# TraitementNumerique.net
KiCad netlist of a schematic drawn in Altium Designer
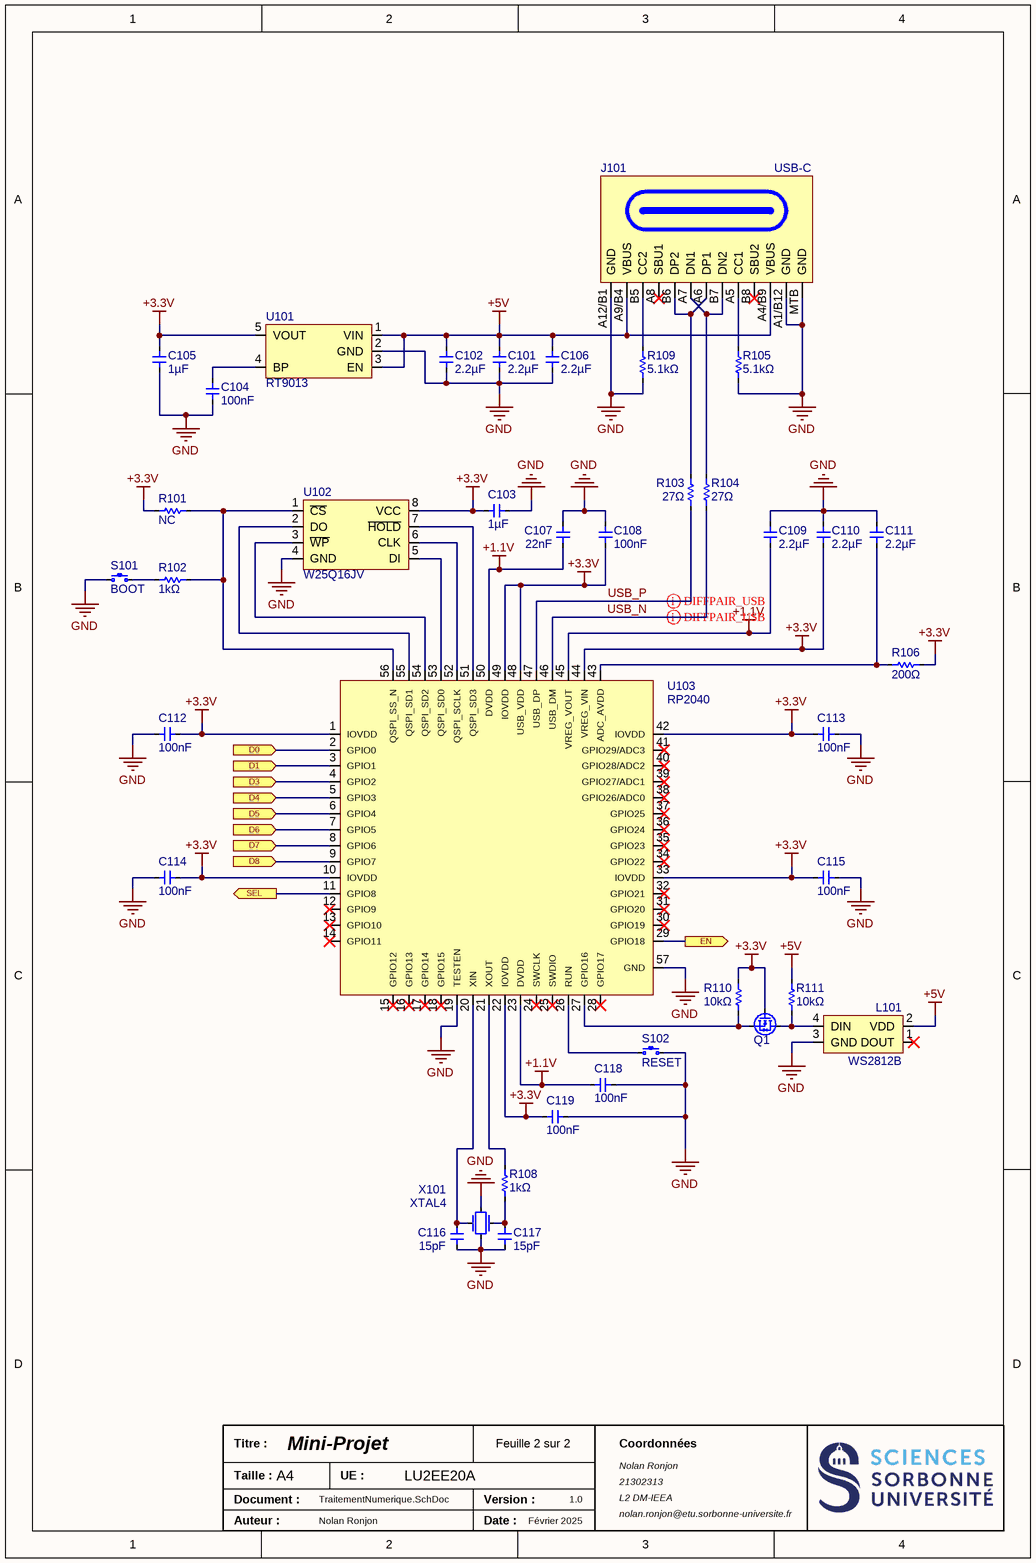
[diagram p0: TraitementNumerique.SchDoc]

(export (version "E")
  (design (tool "Eeschema 10.0.6"))
  (components
    (comp (ref "C101")
      (value "2.2µF")
      (footprint "0603")
      (description "Condensateur")
      (libsource (lib "LU2EE20A") (part "Condensateur"))
    )
    (comp (ref "C102")
      (value "2.2µF")
      (footprint "0603")
      (description "Condensateur")
      (libsource (lib "LU2EE20A") (part "Condensateur"))
    )
    (comp (ref "C103")
      (value "1µF")
      (footprint "0603")
      (description "Condensateur")
      (libsource (lib "LU2EE20A") (part "Condensateur"))
    )
    (comp (ref "C104")
      (value "100nF")
      (footprint "0603")
      (description "Condensateur")
      (libsource (lib "LU2EE20A") (part "Condensateur"))
    )
    (comp (ref "C105")
      (value "1µF")
      (footprint "0603")
      (description "Condensateur")
      (libsource (lib "LU2EE20A") (part "Condensateur"))
    )
    (comp (ref "C106")
      (value "2.2µF")
      (footprint "0603")
      (description "Condensateur")
      (libsource (lib "LU2EE20A") (part "Condensateur"))
    )
    (comp (ref "C107")
      (value "22nF")
      (footprint "0603")
      (description "Condensateur")
      (libsource (lib "LU2EE20A") (part "Condensateur"))
    )
    (comp (ref "C108")
      (value "100nF")
      (footprint "0603")
      (description "Condensateur")
      (libsource (lib "LU2EE20A") (part "Condensateur"))
    )
    (comp (ref "C109")
      (value "2.2µF")
      (footprint "0603")
      (description "Condensateur")
      (libsource (lib "LU2EE20A") (part "Condensateur"))
    )
    (comp (ref "C110")
      (value "2.2µF")
      (footprint "0603")
      (description "Condensateur")
      (libsource (lib "LU2EE20A") (part "Condensateur"))
    )
    (comp (ref "C111")
      (value "2.2µF")
      (footprint "0603")
      (description "Condensateur")
      (libsource (lib "LU2EE20A") (part "Condensateur"))
    )
    (comp (ref "C112")
      (value "100nF")
      (footprint "0603")
      (description "Condensateur")
      (libsource (lib "LU2EE20A") (part "Condensateur"))
    )
    (comp (ref "C113")
      (value "100nF")
      (footprint "0603")
      (description "Condensateur")
      (libsource (lib "LU2EE20A") (part "Condensateur"))
    )
    (comp (ref "C114")
      (value "100nF")
      (footprint "0603")
      (description "Condensateur")
      (libsource (lib "LU2EE20A") (part "Condensateur"))
    )
    (comp (ref "C115")
      (value "100nF")
      (footprint "0603")
      (description "Condensateur")
      (libsource (lib "LU2EE20A") (part "Condensateur"))
    )
    (comp (ref "C116")
      (value "15pF")
      (footprint "0603")
      (description "Condensateur")
      (libsource (lib "LU2EE20A") (part "Condensateur"))
    )
    (comp (ref "C117")
      (value "15pF")
      (footprint "0603")
      (description "Condensateur")
      (libsource (lib "LU2EE20A") (part "Condensateur"))
    )
    (comp (ref "C118")
      (value "100nF")
      (footprint "0603")
      (description "Condensateur")
      (libsource (lib "LU2EE20A") (part "Condensateur"))
    )
    (comp (ref "C119")
      (value "100nF")
      (footprint "0603")
      (description "Condensateur")
      (libsource (lib "LU2EE20A") (part "Condensateur"))
    )
    (comp (ref "J101")
      (value "USB-C")
      (footprint "USB-C")
      (description "Connecteur")
      (fields (field (name "MANUFACTURER PART") "TYPE-C-31-M-12") (field (name "JLCPCB PART") "C165948"))
      (libsource (lib "LU2EE20A") (part "USB-C"))
    )
    (comp (ref "L101")
      (value "WS2812B")
      (footprint "SMD1615")
      (description "LED RGB")
      (fields
        (field (name "MANUFACTURER PART") "XL-1615RGBC-WS2812B")
        (field (name "JLCPCB PART") "C5349954")
      )
      (libsource (lib "LU2EE20A") (part "WS2812B"))
    )
    (comp (ref "Q1")
      (value "2N7002")
      (footprint "SOT-23")
      (description "MOSFET")
      (fields (field (name "MANUFACTURER PART") "2N7002K-7") (field (name "JLCPCB PART") "C85047"))
      (libsource (lib "LU2EE20A") (part "2N7002"))
    )
    (comp (ref "R101")
      (value "NC")
      (footprint "0603")
      (description "Resistance")
      (libsource (lib "LU2EE20A") (part "Resistance"))
    )
    (comp (ref "R102")
      (value "1kΩ")
      (footprint "0603")
      (description "Resistance")
      (libsource (lib "LU2EE20A") (part "Resistance"))
    )
    (comp (ref "R103")
      (value "27Ω")
      (footprint "0603")
      (description "Resistance")
      (libsource (lib "LU2EE20A") (part "Resistance"))
    )
    (comp (ref "R104")
      (value "27Ω")
      (footprint "0603")
      (description "Resistance")
      (libsource (lib "LU2EE20A") (part "Resistance"))
    )
    (comp (ref "R105")
      (value "5.1kΩ")
      (footprint "0603")
      (description "Resistance")
      (libsource (lib "LU2EE20A") (part "Resistance"))
    )
    (comp (ref "R106")
      (value "200Ω")
      (footprint "0603")
      (description "Resistance")
      (libsource (lib "LU2EE20A") (part "Resistance"))
    )
    (comp (ref "R108")
      (value "1kΩ")
      (footprint "0603")
      (description "Resistance")
      (libsource (lib "LU2EE20A") (part "Resistance"))
    )
    (comp (ref "R109")
      (value "5.1kΩ")
      (footprint "0603")
      (description "Resistance")
      (libsource (lib "LU2EE20A") (part "Resistance"))
    )
    (comp (ref "R110")
      (value "10kΩ")
      (footprint "0603")
      (description "Resistance")
      (libsource (lib "LU2EE20A") (part "Resistance"))
    )
    (comp (ref "R111")
      (value "10kΩ")
      (footprint "0603")
      (description "Resistance")
      (libsource (lib "LU2EE20A") (part "Resistance"))
    )
    (comp (ref "S101")
      (value "BOOT")
      (footprint "Bouton")
      (description "Bouton")
      (fields (field (name "MANUFACTURER PART") "TS-1088-AR02016") (field (name "JLCPCB PART") "C720477"))
      (libsource (lib "LU2EE20A") (part "Bouton"))
    )
    (comp (ref "S102")
      (value "RESET")
      (footprint "Bouton")
      (description "Bouton")
      (fields (field (name "MANUFACTURER PART") "TS-1088-AR02016") (field (name "JLCPCB PART") "C720477"))
      (libsource (lib "LU2EE20A") (part "Bouton"))
    )
    (comp (ref "U101")
      (value "RT9013")
      (footprint "SOT-23-5")
      (description "Régulateur de tension")
      (fields (field (name "MANUFACTURER PART") "RT9013-33GB") (field (name "JLCPCB PART") "C47773"))
      (libsource (lib "LU2EE20A") (part "RT9013"))
    )
    (comp (ref "U102")
      (value "W25Q16JV")
      (footprint "USON-8")
      (description "Flash")
      (fields (field (name "MANUFACTURER PART") "W25Q16JVUXIQ") (field (name "JLCPCB PART") "C2843335"))
      (libsource (lib "LU2EE20A") (part "W25Q16JV"))
    )
    (comp (ref "U103")
      (value "RP2040")
      (footprint "QFN-56")
      (description "Microcontroleur")
      (fields (field (name "JLCPCB PART") "C2040"))
      (libsource (lib "LU2EE20A") (part "RP2040"))
    )
    (comp (ref "X101")
      (value "XTAL4")
      (footprint "SMD3225")
      (description "Crystal")
      (fields (field (name "MANUFACTURER PART") "ABM8-272-T3") (field (name "JLCPCB PART") "C20625731"))
      (libsource (lib "LU2EE20A") (part "XTAL4"))
    )
  )
  (nets
    (net (code "1") (name "+1.1V") (class "Default")
      (node (ref "C107") (pin "2") (pinfunction "2_2") (pintype "passive"))
      (node (ref "C109") (pin "2") (pinfunction "2_2") (pintype "passive"))
      (node (ref "C118") (pin "2") (pinfunction "2_2") (pintype "passive"))
      (node (ref "U103") (pin "23") (pinfunction "DVDD_23") (pintype "passive"))
      (node (ref "U103") (pin "45") (pinfunction "VREG_VOUT_45") (pintype "passive"))
      (node (ref "U103") (pin "50") (pinfunction "DVDD_50") (pintype "passive"))
    )
    (net (code "2") (name "+3.3V") (class "Default")
      (node (ref "C103") (pin "2") (pinfunction "2_2") (pintype "passive"))
      (node (ref "C105") (pin "1") (pinfunction "1_1") (pintype "passive"))
      (node (ref "C108") (pin "2") (pinfunction "2_2") (pintype "passive"))
      (node (ref "C110") (pin "2") (pinfunction "2_2") (pintype "passive"))
      (node (ref "C112") (pin "2") (pinfunction "2_2") (pintype "passive"))
      (node (ref "C113") (pin "2") (pinfunction "2_2") (pintype "passive"))
      (node (ref "C114") (pin "2") (pinfunction "2_2") (pintype "passive"))
      (node (ref "C115") (pin "2") (pinfunction "2_2") (pintype "passive"))
      (node (ref "C119") (pin "2") (pinfunction "2_2") (pintype "passive"))
      (node (ref "Q1") (pin "1") (pinfunction "G_1") (pintype "passive"))
      (node (ref "R101") (pin "2") (pinfunction "2_2") (pintype "passive"))
      (node (ref "R106") (pin "1") (pinfunction "1_1") (pintype "passive"))
      (node (ref "R110") (pin "2") (pinfunction "2_2") (pintype "passive"))
      (node (ref "U101") (pin "5") (pinfunction "VOUT_5") (pintype "passive"))
      (node (ref "U102") (pin "8") (pinfunction "VCC_8") (pintype "passive"))
      (node (ref "U103") (pin "1") (pinfunction "IOVDD_1") (pintype "passive"))
      (node (ref "U103") (pin "10") (pinfunction "IOVDD_10") (pintype "passive"))
      (node (ref "U103") (pin "22") (pinfunction "IOVDD_22") (pintype "passive"))
      (node (ref "U103") (pin "33") (pinfunction "IOVDD_33") (pintype "passive"))
      (node (ref "U103") (pin "42") (pinfunction "IOVDD_42") (pintype "passive"))
      (node (ref "U103") (pin "44") (pinfunction "VREG_VIN_44") (pintype "passive"))
      (node (ref "U103") (pin "48") (pinfunction "USB_VDD_48") (pintype "passive"))
      (node (ref "U103") (pin "49") (pinfunction "IOVDD_49") (pintype "passive"))
    )
    (net (code "3") (name "+5V") (class "Default")
      (node (ref "C101") (pin "1") (pinfunction "1_1") (pintype "passive"))
      (node (ref "C102") (pin "1") (pinfunction "1_1") (pintype "passive"))
      (node (ref "C106") (pin "1") (pinfunction "1_1") (pintype "passive"))
      (node (ref "J101") (pin "A4/B9") (pinfunction "VBUS_A4/B9") (pintype "passive"))
      (node (ref "J101") (pin "A9/B4") (pinfunction "VBUS_A9/B4") (pintype "passive"))
      (node (ref "L101") (pin "2") (pinfunction "VDD_2") (pintype "passive"))
      (node (ref "R111") (pin "2") (pinfunction "2_2") (pintype "passive"))
      (node (ref "U101") (pin "1") (pinfunction "VIN_1") (pintype "passive"))
      (node (ref "U101") (pin "3") (pinfunction "EN_3") (pintype "passive"))
    )
    (net (code "4") (name "/D0") (class "Default")
      (node (ref "U103") (pin "2") (pinfunction "GPIO0_2") (pintype "passive"))
    )
    (net (code "5") (name "/D1") (class "Default")
      (node (ref "U103") (pin "3") (pinfunction "GPIO1_3") (pintype "passive"))
    )
    (net (code "6") (name "/D3") (class "Default")
      (node (ref "U103") (pin "4") (pinfunction "GPIO2_4") (pintype "passive"))
    )
    (net (code "7") (name "/D4") (class "Default")
      (node (ref "U103") (pin "5") (pinfunction "GPIO3_5") (pintype "passive"))
    )
    (net (code "8") (name "/D5") (class "Default")
      (node (ref "U103") (pin "6") (pinfunction "GPIO4_6") (pintype "passive"))
    )
    (net (code "9") (name "/D6") (class "Default")
      (node (ref "U103") (pin "7") (pinfunction "GPIO5_7") (pintype "passive"))
    )
    (net (code "10") (name "/D7") (class "Default")
      (node (ref "U103") (pin "8") (pinfunction "GPIO6_8") (pintype "passive"))
    )
    (net (code "11") (name "/D8") (class "Default")
      (node (ref "U103") (pin "9") (pinfunction "GPIO7_9") (pintype "passive"))
    )
    (net (code "12") (name "/EN") (class "Default")
      (node (ref "U103") (pin "29") (pinfunction "GPIO18_29") (pintype "passive"))
    )
    (net (code "13") (name "/SEL") (class "Default")
      (node (ref "U103") (pin "11") (pinfunction "GPIO8_11") (pintype "passive"))
    )
    (net (code "14") (name "/USB_N") (class "Default")
      (node (ref "R104") (pin "1") (pinfunction "1_1") (pintype "passive"))
      (node (ref "U103") (pin "46") (pinfunction "USB_DM_46") (pintype "passive"))
    )
    (net (code "15") (name "/USB_P") (class "Default")
      (node (ref "R103") (pin "1") (pinfunction "1_1") (pintype "passive"))
      (node (ref "U103") (pin "47") (pinfunction "USB_DP_47") (pintype "passive"))
    )
    (net (code "16") (name "GND") (class "Default")
      (node (ref "C101") (pin "2") (pinfunction "2_2") (pintype "passive"))
      (node (ref "C102") (pin "2") (pinfunction "2_2") (pintype "passive"))
      (node (ref "C103") (pin "1") (pinfunction "1_1") (pintype "passive"))
      (node (ref "C104") (pin "2") (pinfunction "2_2") (pintype "passive"))
      (node (ref "C105") (pin "2") (pinfunction "2_2") (pintype "passive"))
      (node (ref "C106") (pin "2") (pinfunction "2_2") (pintype "passive"))
      (node (ref "C107") (pin "1") (pinfunction "1_1") (pintype "passive"))
      (node (ref "C108") (pin "1") (pinfunction "1_1") (pintype "passive"))
      (node (ref "C109") (pin "1") (pinfunction "1_1") (pintype "passive"))
      (node (ref "C110") (pin "1") (pinfunction "1_1") (pintype "passive"))
      (node (ref "C111") (pin "1") (pinfunction "1_1") (pintype "passive"))
      (node (ref "C112") (pin "1") (pinfunction "1_1") (pintype "passive"))
      (node (ref "C113") (pin "1") (pinfunction "1_1") (pintype "passive"))
      (node (ref "C114") (pin "1") (pinfunction "1_1") (pintype "passive"))
      (node (ref "C115") (pin "1") (pinfunction "1_1") (pintype "passive"))
      (node (ref "C116") (pin "2") (pinfunction "2_2") (pintype "passive"))
      (node (ref "C117") (pin "2") (pinfunction "2_2") (pintype "passive"))
      (node (ref "C118") (pin "1") (pinfunction "1_1") (pintype "passive"))
      (node (ref "C119") (pin "1") (pinfunction "1_1") (pintype "passive"))
      (node (ref "J101") (pin "A1/B12") (pinfunction "GND_A1/B12") (pintype "passive"))
      (node (ref "J101") (pin "A12/B1") (pinfunction "GND_A12/B1") (pintype "passive"))
      (node (ref "J101") (pin "MTB") (pinfunction "GND_MTB") (pintype "passive"))
      (node (ref "L101") (pin "3") (pinfunction "GND_3") (pintype "passive"))
      (node (ref "R105") (pin "1") (pinfunction "1_1") (pintype "passive"))
      (node (ref "R109") (pin "1") (pinfunction "1_1") (pintype "passive"))
      (node (ref "S101") (pin "1") (pinfunction "1_1") (pintype "passive"))
      (node (ref "S102") (pin "2") (pinfunction "2_2") (pintype "passive"))
      (node (ref "U101") (pin "2") (pinfunction "GND_2") (pintype "passive"))
      (node (ref "U102") (pin "4") (pinfunction "GND_4") (pintype "passive"))
      (node (ref "U103") (pin "19") (pinfunction "TESTEN_19") (pintype "passive"))
      (node (ref "U103") (pin "57") (pinfunction "GND_57") (pintype "passive"))
      (node (ref "X101") (pin "2") (pinfunction "GND_1_2") (pintype "passive"))
      (node (ref "X101") (pin "4") (pinfunction "GND_2_4") (pintype "passive"))
    )
    (net (code "17") (name "Net-(J101-CC1)") (class "Default")
      (node (ref "J101") (pin "A5") (pinfunction "CC1_A5") (pintype "passive"))
      (node (ref "R105") (pin "2") (pinfunction "2_2") (pintype "passive"))
    )
    (net (code "18") (name "Net-(J101-CC2)") (class "Default")
      (node (ref "J101") (pin "B5") (pinfunction "CC2_B5") (pintype "passive"))
      (node (ref "R109") (pin "2") (pinfunction "2_2") (pintype "passive"))
    )
    (net (code "19") (name "Net-(J101-DN1)") (class "Default")
      (node (ref "J101") (pin "A7") (pinfunction "DN1_A7") (pintype "passive"))
      (node (ref "J101") (pin "B7") (pinfunction "DN2_B7") (pintype "passive"))
      (node (ref "R104") (pin "2") (pinfunction "2_2") (pintype "passive"))
    )
    (net (code "20") (name "Net-(J101-DP1)") (class "Default")
      (node (ref "J101") (pin "A6") (pinfunction "DP1_A6") (pintype "passive"))
      (node (ref "J101") (pin "B6") (pinfunction "DP2_B6") (pintype "passive"))
      (node (ref "R103") (pin "2") (pinfunction "2_2") (pintype "passive"))
    )
    (net (code "21") (name "Net-(L101-DIN)") (class "Default")
      (node (ref "L101") (pin "4") (pinfunction "DIN_4") (pintype "passive"))
      (node (ref "Q1") (pin "3") (pinfunction "D_3") (pintype "passive"))
      (node (ref "R111") (pin "1") (pinfunction "1_1") (pintype "passive"))
    )
    (net (code "22") (name "Net-(Q1-S)") (class "Default")
      (node (ref "Q1") (pin "2") (pinfunction "S_2") (pintype "passive"))
      (node (ref "R110") (pin "1") (pinfunction "1_1") (pintype "passive"))
      (node (ref "U103") (pin "27") (pinfunction "GPIO16_27") (pintype "passive"))
    )
    (net (code "23") (name "Net-(R102-Pad2)") (class "Default")
      (node (ref "R102") (pin "2") (pinfunction "2_2") (pintype "passive"))
      (node (ref "S101") (pin "2") (pinfunction "2_2") (pintype "passive"))
    )
    (net (code "24") (name "Net-(U101-BP)") (class "Default")
      (node (ref "C104") (pin "1") (pinfunction "1_1") (pintype "passive"))
      (node (ref "U101") (pin "4") (pinfunction "BP_4") (pintype "passive"))
    )
    (net (code "25") (name "Net-(U102-CLK)") (class "Default")
      (node (ref "U102") (pin "6") (pinfunction "CLK_6") (pintype "passive"))
      (node (ref "U103") (pin "52") (pinfunction "QSPI_SCLK_52") (pintype "passive"))
    )
    (net (code "26") (name "Net-(U102-CS)") (class "Default")
      (node (ref "R101") (pin "1") (pinfunction "1_1") (pintype "passive"))
      (node (ref "R102") (pin "1") (pinfunction "1_1") (pintype "passive"))
      (node (ref "U102") (pin "1") (pinfunction "CS_1") (pintype "passive"))
      (node (ref "U103") (pin "56") (pinfunction "QSPI_SS_N_56") (pintype "passive"))
    )
    (net (code "27") (name "Net-(U102-DI)") (class "Default")
      (node (ref "U102") (pin "5") (pinfunction "DI_5") (pintype "passive"))
      (node (ref "U103") (pin "53") (pinfunction "QSPI_SD0_53") (pintype "passive"))
    )
    (net (code "28") (name "Net-(U102-DO)") (class "Default")
      (node (ref "U102") (pin "2") (pinfunction "DO_2") (pintype "passive"))
      (node (ref "U103") (pin "55") (pinfunction "QSPI_SD1_55") (pintype "passive"))
    )
    (net (code "29") (name "Net-(U102-HOLD)") (class "Default")
      (node (ref "U102") (pin "7") (pinfunction "HOLD_7") (pintype "passive"))
      (node (ref "U103") (pin "51") (pinfunction "QSPI_SD3_51") (pintype "passive"))
    )
    (net (code "30") (name "Net-(U102-WP)") (class "Default")
      (node (ref "U102") (pin "3") (pinfunction "WP_3") (pintype "passive"))
      (node (ref "U103") (pin "54") (pinfunction "QSPI_SD2_54") (pintype "passive"))
    )
    (net (code "31") (name "Net-(U103-ADC_AVDD)") (class "Default")
      (node (ref "C111") (pin "2") (pinfunction "2_2") (pintype "passive"))
      (node (ref "R106") (pin "2") (pinfunction "2_2") (pintype "passive"))
      (node (ref "U103") (pin "43") (pinfunction "ADC_AVDD_43") (pintype "passive"))
    )
    (net (code "32") (name "Net-(U103-RUN)") (class "Default")
      (node (ref "S102") (pin "1") (pinfunction "1_1") (pintype "passive"))
      (node (ref "U103") (pin "26") (pinfunction "RUN_26") (pintype "passive"))
    )
    (net (code "33") (name "Net-(U103-XIN)") (class "Default")
      (node (ref "C116") (pin "1") (pinfunction "1_1") (pintype "passive"))
      (node (ref "U103") (pin "20") (pinfunction "XIN_20") (pintype "passive"))
      (node (ref "X101") (pin "1") (pinfunction "CRYSTAL_1_1") (pintype "passive"))
    )
    (net (code "34") (name "Net-(U103-XOUT)") (class "Default")
      (node (ref "R108") (pin "2") (pinfunction "2_2") (pintype "passive"))
      (node (ref "U103") (pin "21") (pinfunction "XOUT_21") (pintype "passive"))
    )
    (net (code "35") (name "Net-(X101-CRYSTAL_2)") (class "Default")
      (node (ref "C117") (pin "1") (pinfunction "1_1") (pintype "passive"))
      (node (ref "R108") (pin "1") (pinfunction "1_1") (pintype "passive"))
      (node (ref "X101") (pin "3") (pinfunction "CRYSTAL_2_3") (pintype "passive"))
    )
    (net (code "36") (name "unconnected-(J101-SBU1-PadA8)") (class "Default")
      (node (ref "J101") (pin "A8") (pinfunction "SBU1_A8") (pintype "passive+no_connect"))
    )
    (net (code "37") (name "unconnected-(J101-SBU2-PadB8)") (class "Default")
      (node (ref "J101") (pin "B8") (pinfunction "SBU2_B8") (pintype "passive+no_connect"))
    )
    (net (code "38") (name "unconnected-(L101-DOUT-Pad1)") (class "Default")
      (node (ref "L101") (pin "1") (pinfunction "DOUT_1") (pintype "passive+no_connect"))
    )
    (net (code "39") (name "unconnected-(U103-GPIO9-Pad12)") (class "Default")
      (node (ref "U103") (pin "12") (pinfunction "GPIO9_12") (pintype "passive+no_connect"))
    )
    (net (code "40") (name "unconnected-(U103-GPIO10-Pad13)") (class "Default")
      (node (ref "U103") (pin "13") (pinfunction "GPIO10_13") (pintype "passive+no_connect"))
    )
    (net (code "41") (name "unconnected-(U103-GPIO11-Pad14)") (class "Default")
      (node (ref "U103") (pin "14") (pinfunction "GPIO11_14") (pintype "passive+no_connect"))
    )
    (net (code "42") (name "unconnected-(U103-GPIO12-Pad15)") (class "Default")
      (node (ref "U103") (pin "15") (pinfunction "GPIO12_15") (pintype "passive+no_connect"))
    )
    (net (code "43") (name "unconnected-(U103-GPIO13-Pad16)") (class "Default")
      (node (ref "U103") (pin "16") (pinfunction "GPIO13_16") (pintype "passive+no_connect"))
    )
    (net (code "44") (name "unconnected-(U103-GPIO14-Pad17)") (class "Default")
      (node (ref "U103") (pin "17") (pinfunction "GPIO14_17") (pintype "passive+no_connect"))
    )
    (net (code "45") (name "unconnected-(U103-GPIO15-Pad18)") (class "Default")
      (node (ref "U103") (pin "18") (pinfunction "GPIO15_18") (pintype "passive+no_connect"))
    )
    (net (code "46") (name "unconnected-(U103-GPIO17-Pad28)") (class "Default")
      (node (ref "U103") (pin "28") (pinfunction "GPIO17_28") (pintype "passive+no_connect"))
    )
    (net (code "47") (name "unconnected-(U103-GPIO19-Pad30)") (class "Default")
      (node (ref "U103") (pin "30") (pinfunction "GPIO19_30") (pintype "passive+no_connect"))
    )
    (net (code "48") (name "unconnected-(U103-GPIO20-Pad31)") (class "Default")
      (node (ref "U103") (pin "31") (pinfunction "GPIO20_31") (pintype "passive+no_connect"))
    )
    (net (code "49") (name "unconnected-(U103-GPIO21-Pad32)") (class "Default")
      (node (ref "U103") (pin "32") (pinfunction "GPIO21_32") (pintype "passive+no_connect"))
    )
    (net (code "50") (name "unconnected-(U103-GPIO22-Pad34)") (class "Default")
      (node (ref "U103") (pin "34") (pinfunction "GPIO22_34") (pintype "passive+no_connect"))
    )
    (net (code "51") (name "unconnected-(U103-GPIO23-Pad35)") (class "Default")
      (node (ref "U103") (pin "35") (pinfunction "GPIO23_35") (pintype "passive+no_connect"))
    )
    (net (code "52") (name "unconnected-(U103-GPIO24-Pad36)") (class "Default")
      (node (ref "U103") (pin "36") (pinfunction "GPIO24_36") (pintype "passive+no_connect"))
    )
    (net (code "53") (name "unconnected-(U103-GPIO25-Pad37)") (class "Default")
      (node (ref "U103") (pin "37") (pinfunction "GPIO25_37") (pintype "passive+no_connect"))
    )
    (net (code "54") (name "unconnected-(U103-GPIO26{slash}ADC0-Pad38)") (class "Default")
      (node (ref "U103") (pin "38") (pinfunction "GPIO26/ADC0_38") (pintype "passive+no_connect"))
    )
    (net (code "55") (name "unconnected-(U103-GPIO27{slash}ADC1-Pad39)") (class "Default")
      (node (ref "U103") (pin "39") (pinfunction "GPIO27/ADC1_39") (pintype "passive+no_connect"))
    )
    (net (code "56") (name "unconnected-(U103-GPIO28{slash}ADC2-Pad40)") (class "Default")
      (node (ref "U103") (pin "40") (pinfunction "GPIO28/ADC2_40") (pintype "passive+no_connect"))
    )
    (net (code "57") (name "unconnected-(U103-GPIO29{slash}ADC3-Pad41)") (class "Default")
      (node (ref "U103") (pin "41") (pinfunction "GPIO29/ADC3_41") (pintype "passive+no_connect"))
    )
    (net (code "58") (name "unconnected-(U103-SWCLK-Pad24)") (class "Default")
      (node (ref "U103") (pin "24") (pinfunction "SWCLK_24") (pintype "passive+no_connect"))
    )
    (net (code "59") (name "unconnected-(U103-SWDIO-Pad25)") (class "Default")
      (node (ref "U103") (pin "25") (pinfunction "SWDIO_25") (pintype "passive+no_connect"))
    )
  )
)
